# Sheet.net
KiCad netlist of a schematic drawn in Altium Designer
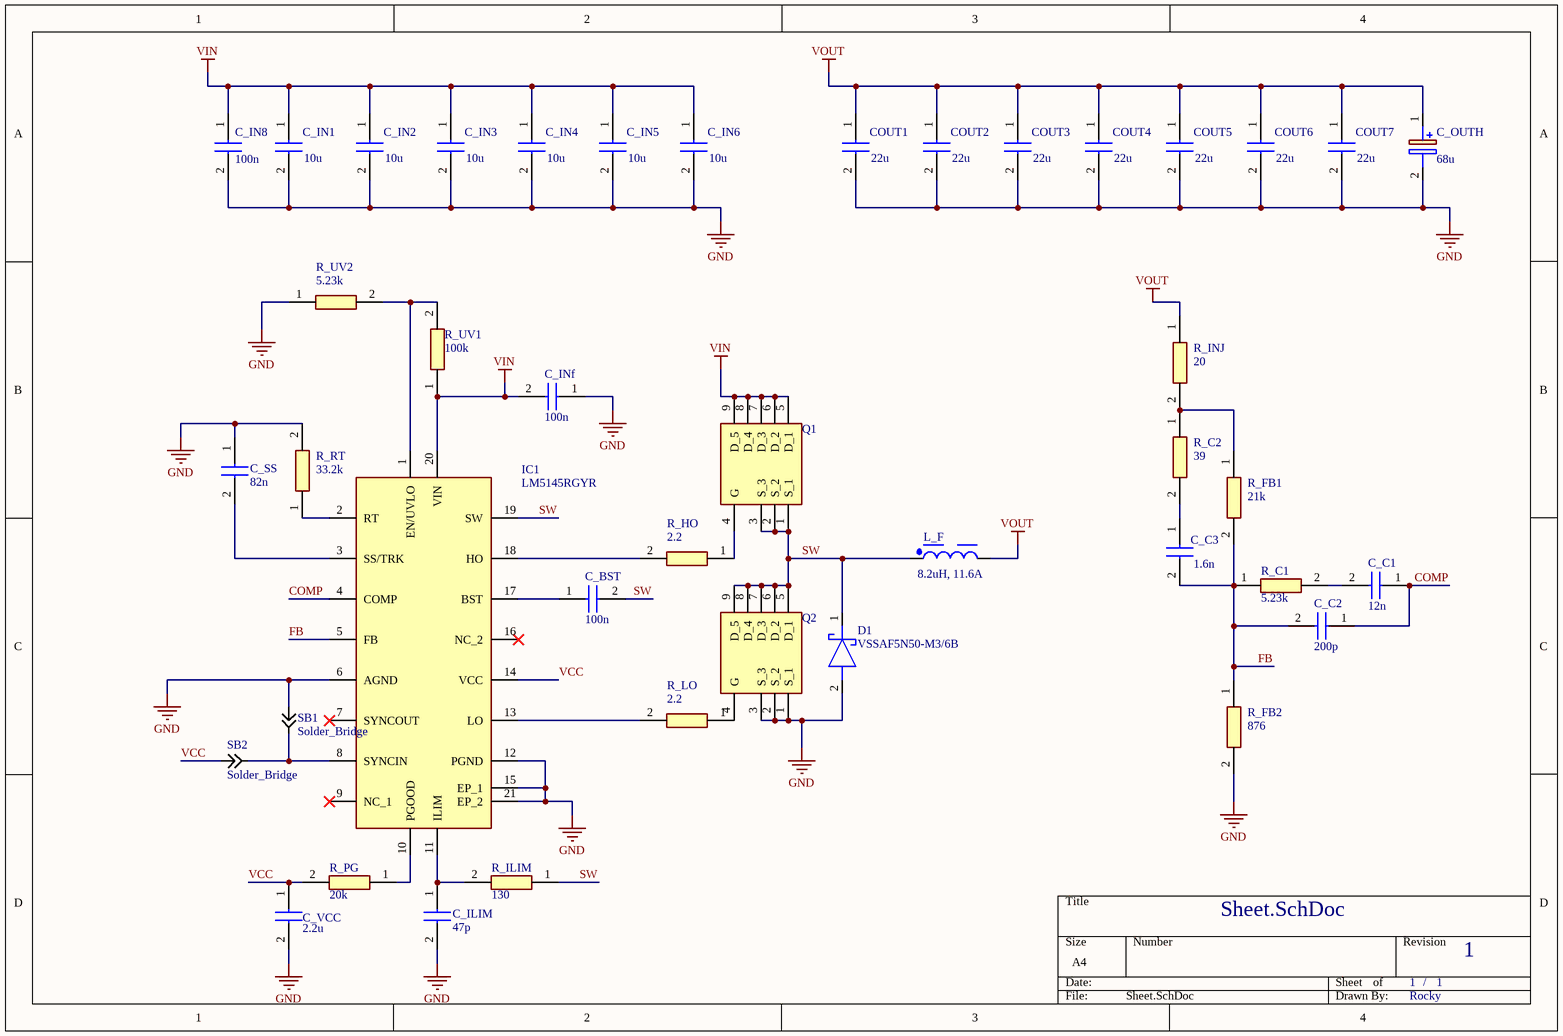
[diagram p0: Sheet.SchDoc]

(export (version "E")
  (design (tool "Eeschema 10.0.6"))
  (components
    (comp (ref "COUT1")
      (value "22u")
      (footprint "PcbLib:CAPC6153X390N")
      (description "Capacitor\r\nKCM55QR71H226KH13K")
      (fields
        (field (name "MANUFACTURER_PART_NUMBER") "KCM55QR71H226KH13K")
        (field (name "MOUSER PART NUMBER") "81-KCM5QR71H226KH13K")
      )
      (libsource (lib "*") (part "KCM55QR71H226KH13K"))
    )
    (comp (ref "COUT2")
      (value "22u")
      (footprint "PcbLib:CAPC6153X390N")
      (description "Capacitor\r\nKCM55QR71H226KH13K")
      (fields
        (field (name "MANUFACTURER_PART_NUMBER") "KCM55QR71H226KH13K")
        (field (name "MOUSER PART NUMBER") "81-KCM5QR71H226KH13K")
      )
      (libsource (lib "*") (part "KCM55QR71H226KH13K"))
    )
    (comp (ref "COUT3")
      (value "22u")
      (footprint "PcbLib:CAPC6153X390N")
      (description "Capacitor\r\nKCM55QR71H226KH13K")
      (fields
        (field (name "MANUFACTURER_PART_NUMBER") "KCM55QR71H226KH13K")
        (field (name "MOUSER PART NUMBER") "81-KCM5QR71H226KH13K")
      )
      (libsource (lib "*") (part "KCM55QR71H226KH13K"))
    )
    (comp (ref "COUT4")
      (value "22u")
      (footprint "PcbLib:CAPC6153X390N")
      (description "Capacitor\r\nKCM55QR71H226KH13K")
      (fields
        (field (name "MANUFACTURER_PART_NUMBER") "KCM55QR71H226KH13K")
        (field (name "MOUSER PART NUMBER") "81-KCM5QR71H226KH13K")
      )
      (libsource (lib "*") (part "KCM55QR71H226KH13K"))
    )
    (comp (ref "COUT5")
      (value "22u")
      (footprint "PcbLib:CAPC6153X390N")
      (description "Capacitor\r\nKCM55QR71H226KH13K")
      (fields
        (field (name "MANUFACTURER_PART_NUMBER") "KCM55QR71H226KH13K")
        (field (name "MOUSER PART NUMBER") "81-KCM5QR71H226KH13K")
      )
      (libsource (lib "*") (part "KCM55QR71H226KH13K"))
    )
    (comp (ref "COUT6")
      (value "22u")
      (footprint "PcbLib:CAPC6153X390N")
      (description "Capacitor\r\nKCM55QR71H226KH13K")
      (fields
        (field (name "MANUFACTURER_PART_NUMBER") "KCM55QR71H226KH13K")
        (field (name "MOUSER PART NUMBER") "81-KCM5QR71H226KH13K")
      )
      (libsource (lib "*") (part "KCM55QR71H226KH13K"))
    )
    (comp (ref "COUT7")
      (value "22u")
      (footprint "PcbLib:CAPC6153X390N")
      (description "Capacitor\r\nKCM55QR71H226KH13K")
      (fields
        (field (name "MANUFACTURER_PART_NUMBER") "KCM55QR71H226KH13K")
        (field (name "MOUSER PART NUMBER") "81-KCM5QR71H226KH13K")
      )
      (libsource (lib "*") (part "KCM55QR71H226KH13K"))
    )
    (comp (ref "C_BST")
      (value "100n")
      (footprint "PcbLib:CAPC1608X90N")
      (description "Capacitor")
      (fields
        (field (name "MANUFACTURER_PART_NUMBER") "GRM1885C1H101JA01D")
        (field (name "MOUSER PART NUMBER") "81-GRM39C101J50")
      )
      (libsource (lib "Schlib") (part "GRM1885C1H101JA01D"))
    )
    (comp (ref "C_C1")
      (value "12n")
      (footprint "PcbLib:CAPC1608X90N")
      (description "Capacitor")
      (fields
        (field (name "MANUFACTURER_PART_NUMBER") "06031A470JAT2A")
        (field (name "MOUSER PART NUMBER") "581-06031A470J")
      )
      (libsource (lib "*") (part "06031A470JAT2A"))
    )
    (comp (ref "C_C2")
      (value "200p")
      (footprint "PcbLib:CAPC1608X90N")
      (description "Capacitor")
      (fields
        (field (name "MANUFACTURER_PART_NUMBER") "06031A470JAT2A")
        (field (name "MOUSER PART NUMBER") "581-06031A470J")
      )
      (libsource (lib "*") (part "06031A470JAT2A"))
    )
    (comp (ref "C_C3")
      (value "1.6n")
      (footprint "PcbLib:CAPC1608X90N")
      (description "Capacitor")
      (fields
        (field (name "MANUFACTURER_PART_NUMBER") "06031A470JAT2A")
        (field (name "MOUSER PART NUMBER") "581-06031A470J")
      )
      (libsource (lib "*") (part "06031A470JAT2A"))
    )
    (comp (ref "C_ILIM")
      (value "47p")
      (footprint "PcbLib:CAPC1608X90N")
      (description "Capacitor")
      (fields
        (field (name "MANUFACTURER_PART_NUMBER") "06031A470JAT2A")
        (field (name "MOUSER PART NUMBER") "581-06031A470J")
      )
      (libsource (lib "*") (part "06031A470JAT2A"))
    )
    (comp (ref "C_IN1")
      (value "10u")
      (footprint "PcbLib:CAPC6153X390N")
      (description "Capacitor\r\nKRM55QR71J106KH01K")
      (fields
        (field (name "MANUFACTURER_PART_NUMBER") "KRM55QR71J106KH01K")
        (field (name "MOUSER PART NUMBER") "81-KRM55QR71J106KH1K")
      )
      (libsource (lib "*") (part "KRM55QR71J106KH01K"))
    )
    (comp (ref "C_IN2")
      (value "10u")
      (footprint "PcbLib:CAPC6153X390N")
      (description "Capacitor\r\nKRM55QR71J106KH01K")
      (fields
        (field (name "MANUFACTURER_PART_NUMBER") "KRM55QR71J106KH01K")
        (field (name "MOUSER PART NUMBER") "81-KRM55QR71J106KH1K")
      )
      (libsource (lib "*") (part "KRM55QR71J106KH01K"))
    )
    (comp (ref "C_IN3")
      (value "10u")
      (footprint "PcbLib:CAPC6153X390N")
      (description "Capacitor\r\nKRM55QR71J106KH01K")
      (fields
        (field (name "MANUFACTURER_PART_NUMBER") "KRM55QR71J106KH01K")
        (field (name "MOUSER PART NUMBER") "81-KRM55QR71J106KH1K")
      )
      (libsource (lib "*") (part "KRM55QR71J106KH01K"))
    )
    (comp (ref "C_IN4")
      (value "10u")
      (footprint "PcbLib:CAPC6153X390N")
      (description "Capacitor\r\nKRM55QR71J106KH01K")
      (fields
        (field (name "MANUFACTURER_PART_NUMBER") "KRM55QR71J106KH01K")
        (field (name "MOUSER PART NUMBER") "81-KRM55QR71J106KH1K")
      )
      (libsource (lib "*") (part "KRM55QR71J106KH01K"))
    )
    (comp (ref "C_IN5")
      (value "10u")
      (footprint "PcbLib:CAPC6153X390N")
      (description "Capacitor\r\nKRM55QR71J106KH01K")
      (fields
        (field (name "MANUFACTURER_PART_NUMBER") "KRM55QR71J106KH01K")
        (field (name "MOUSER PART NUMBER") "81-KRM55QR71J106KH1K")
      )
      (libsource (lib "*") (part "KRM55QR71J106KH01K"))
    )
    (comp (ref "C_IN6")
      (value "10u")
      (footprint "PcbLib:CAPC6153X390N")
      (description "Capacitor\r\nKRM55QR71J106KH01K")
      (fields
        (field (name "MANUFACTURER_PART_NUMBER") "KRM55QR71J106KH01K")
        (field (name "MOUSER PART NUMBER") "81-KRM55QR71J106KH1K")
      )
      (libsource (lib "*") (part "KRM55QR71J106KH01K"))
    )
    (comp (ref "C_IN8")
      (value "100n")
      (footprint "PcbLib:CAPC1608X90N")
      (description "Capacitor")
      (fields
        (field (name "MANUFACTURER_PART_NUMBER") "GRM1885C1H101JA01D")
        (field (name "MOUSER PART NUMBER") "81-GRM39C101J50")
      )
      (libsource (lib "Schlib") (part "GRM1885C1H101JA01D"))
    )
    (comp (ref "C_INf")
      (value "100n")
      (footprint "PcbLib:CAPC1608X90N")
      (description "Capacitor")
      (fields
        (field (name "MANUFACTURER_PART_NUMBER") "GRM1885C1H101JA01D")
        (field (name "MOUSER PART NUMBER") "81-GRM39C101J50")
      )
      (libsource (lib "Schlib") (part "GRM1885C1H101JA01D"))
    )
    (comp (ref "C_OUTH")
      (value "68u")
      (footprint "PcbLib:35TQS68ME2")
      (description "Capacitor Polarised")
      (fields (field (name "MANUFACTURER_PART_NUMBER") "35TQS68ME2"))
      (libsource (lib "*") (part "35TQS68ME2"))
    )
    (comp (ref "C_SS")
      (value "82n")
      (footprint "PcbLib:CAPC1608X90N")
      (description "Capacitor")
      (fields
        (field (name "MANUFACTURER_PART_NUMBER") "GRM1885C1H101JA01D")
        (field (name "MOUSER PART NUMBER") "81-GRM39C101J50")
      )
      (libsource (lib "Schlib") (part "GRM1885C1H101JA01D"))
    )
    (comp (ref "C_VCC")
      (value "2.2u")
      (footprint "PcbLib:CAPC1608X90N")
      (description "Capacitor")
      (fields
        (field (name "MANUFACTURER_PART_NUMBER") "06031A470JAT2A")
        (field (name "MOUSER PART NUMBER") "581-06031A470J")
      )
      (libsource (lib "*") (part "06031A470JAT2A"))
    )
    (comp (ref "D1")
      (value "VSSAF5N50-M3/6B")
      (footprint "PcbLib:SODFL5226X100N")
      (description "Schottky Diode")
      (fields
        (field (name "MANUFACTURER_PART_NUMBER") "VSSAF3M10-M3/H")
        (field (name "MOUSER PART NUMBER") "78-VSSAF3M10-M3/H")
      )
      (libsource (lib "Schlib") (part "VSSAF3M10-M3_H"))
    )
    (comp (ref "IC1")
      (value "LM5145RGYR")
      (footprint "PcbLib:RGY0020B")
      (description "Integrated Circuit")
      (fields (field (name "MOUSER PART NUMBER") "595-LM5145RGYR"))
      (libsource (lib "Schlib") (part "LM5145RGYR"))
    )
    (comp (ref "L_F")
      (value "8.2uH, 11.6A")
      (footprint "WE-LHCA_1365")
      (description "WE-LHCA Low Profile High Current Inductor, SMT, size 1365, 8.2uH, 11.6A")
      (fields
        (field (name "MANUFACTURER PART NUMBER") "784373865082")
        (field (name "MANUFACTURER") "Wurth Elektronik")
      )
      (libsource (lib "WE - Passive Components") (part "Inductor - 2"))
    )
    (comp (ref "Q1")
      (value "AON6512")
      (footprint "PcbLib:AON6414A")
      (description "MOSFET (P-Channel)")
      (libsource (lib "Schlib") (part "AON6512"))
    )
    (comp (ref "Q2")
      (value "AON6512")
      (footprint "PcbLib:AON6414A")
      (description "MOSFET (P-Channel)")
      (libsource (lib "Schlib") (part "AON6512"))
    )
    (comp (ref "R_C1")
      (value "5.23k")
      (footprint "PcbLib:RESC1608X55N")
      (description "Resistor")
      (fields
        (field (name "MANUFACTURER_PART_NUMBER") "ERJ-3EKF1270V")
        (field (name "MOUSER PART NUMBER") "667-ERJ-3EKF1270V")
      )
      (libsource (lib "") (part "ERJ-3EKF1270V_2"))
    )
    (comp (ref "R_C2")
      (value "39")
      (footprint "PcbLib:RESC1608X55N")
      (description "Resistor")
      (fields
        (field (name "MANUFACTURER_PART_NUMBER") "ERJ-3EKF1270V")
        (field (name "MOUSER PART NUMBER") "667-ERJ-3EKF1270V")
      )
      (libsource (lib "") (part "ERJ-3EKF1270V_1"))
    )
    (comp (ref "R_FB1")
      (value "21k")
      (footprint "PcbLib:RESC1608X55N")
      (description "Resistor")
      (fields
        (field (name "MANUFACTURER_PART_NUMBER") "ERJ-3EKF1270V")
        (field (name "MOUSER PART NUMBER") "667-ERJ-3EKF1270V")
      )
      (libsource (lib "") (part "ERJ-3EKF1270V_1"))
    )
    (comp (ref "R_FB2")
      (value "876")
      (footprint "PcbLib:RESC1608X55N")
      (description "Resistor")
      (fields
        (field (name "MANUFACTURER_PART_NUMBER") "ERJ-3EKF1270V")
        (field (name "MOUSER PART NUMBER") "667-ERJ-3EKF1270V")
      )
      (libsource (lib "") (part "ERJ-3EKF1270V_1"))
    )
    (comp (ref "R_HO")
      (value "2.2")
      (footprint "PcbLib:RESC1608X55N")
      (description "Resistor")
      (fields
        (field (name "MANUFACTURER_PART_NUMBER") "RC0603FR-105K1L")
        (field (name "MOUSER PART NUMBER") "603-RC0603FR-105K1L")
      )
      (libsource (lib "") (part "RC0603FR-105K1L_1"))
    )
    (comp (ref "R_ILIM")
      (value "130")
      (footprint "PcbLib:RESC1608X55N")
      (description "Resistor")
      (fields
        (field (name "MANUFACTURER_PART_NUMBER") "ERJ-3EKF1270V")
        (field (name "MOUSER PART NUMBER") "667-ERJ-3EKF1270V")
      )
      (libsource (lib "*") (part "ERJ-3EKF1270V"))
    )
    (comp (ref "R_INJ")
      (value "20")
      (footprint "PcbLib:RESC1608X55N")
      (description "Resistor")
      (fields
        (field (name "MANUFACTURER_PART_NUMBER") "ERJ-3EKF1270V")
        (field (name "MOUSER PART NUMBER") "667-ERJ-3EKF1270V")
      )
      (libsource (lib "") (part "ERJ-3EKF1270V_1"))
    )
    (comp (ref "R_LO")
      (value "2.2")
      (footprint "PcbLib:RESC1608X55N")
      (description "Resistor")
      (fields
        (field (name "MANUFACTURER_PART_NUMBER") "RC0603FR-105K1L")
        (field (name "MOUSER PART NUMBER") "603-RC0603FR-105K1L")
      )
      (libsource (lib "") (part "RC0603FR-105K1L_1"))
    )
    (comp (ref "R_PG")
      (value "20k")
      (footprint "PcbLib:RESC1608X55N")
      (description "Resistor")
      (fields
        (field (name "MANUFACTURER_PART_NUMBER") "ERJ-3EKF1270V")
        (field (name "MOUSER PART NUMBER") "667-ERJ-3EKF1270V")
      )
      (libsource (lib "*") (part "ERJ-3EKF1270V"))
    )
    (comp (ref "R_RT")
      (value "33.2k")
      (footprint "PcbLib:RESC1608X55N")
      (description "Resistor")
      (fields
        (field (name "MANUFACTURER_PART_NUMBER") "RC0603FR-105K1L")
        (field (name "MOUSER PART NUMBER") "603-RC0603FR-105K1L")
      )
      (libsource (lib "*") (part "RC0603FR-105K1L"))
    )
    (comp (ref "R_UV1")
      (value "100k")
      (footprint "PcbLib:RESC1608X55N")
      (description "Resistor")
      (fields
        (field (name "MANUFACTURER_PART_NUMBER") "RC0603FR-105K1L")
        (field (name "MOUSER PART NUMBER") "603-RC0603FR-105K1L")
      )
      (libsource (lib "Schlib") (part "RC0603FR-105K1L"))
    )
    (comp (ref "R_UV2")
      (value "5.23k")
      (footprint "PcbLib:RESC1608X55N")
      (description "Resistor")
      (fields
        (field (name "MANUFACTURER_PART_NUMBER") "RC0603FR-105K1L")
        (field (name "MOUSER PART NUMBER") "603-RC0603FR-105K1L")
      )
      (libsource (lib "") (part "RC0603FR-105K1L_1"))
    )
    (comp (ref "SB1")
      (value "Solder_Bridge")
      (footprint "Solderbridge")
      (libsource (lib "Schlib") (part "Solder_Bridge"))
    )
    (comp (ref "SB2")
      (value "Solder_Bridge")
      (footprint "Solderbridge")
      (libsource (lib "Schlib") (part "Solder_Bridge"))
    )
  )
  (nets
    (net (code "1") (name "/COMP") (class "Default")
      (node (ref "C_C1") (pin "1") (pinfunction "1_1") (pintype "passive"))
      (node (ref "C_C2") (pin "1") (pinfunction "1_1") (pintype "passive"))
      (node (ref "IC1") (pin "4") (pinfunction "COMP_4") (pintype "passive"))
    )
    (net (code "2") (name "/FB") (class "Default")
      (node (ref "C_C2") (pin "2") (pinfunction "2_2") (pintype "passive"))
      (node (ref "C_C3") (pin "2") (pinfunction "2_2") (pintype "passive"))
      (node (ref "IC1") (pin "5") (pinfunction "FB_5") (pintype "passive"))
      (node (ref "R_C1") (pin "1") (pinfunction "1_1") (pintype "passive"))
      (node (ref "R_FB1") (pin "2") (pinfunction "2_2") (pintype "passive"))
      (node (ref "R_FB2") (pin "1") (pinfunction "1_1") (pintype "passive"))
    )
    (net (code "3") (name "/SW") (class "Default")
      (node (ref "C_BST") (pin "2") (pinfunction "2_2") (pintype "passive"))
      (node (ref "D1") (pin "1") (pinfunction "K_1") (pintype "passive"))
      (node (ref "IC1") (pin "19") (pinfunction "SW_19") (pintype "passive"))
      (node (ref "L_F") (pin "1") (pinfunction "1_1") (pintype "passive"))
      (node (ref "Q1") (pin "1") (pinfunction "S_1_1") (pintype "passive"))
      (node (ref "Q1") (pin "2") (pinfunction "S_2_2") (pintype "passive"))
      (node (ref "Q1") (pin "3") (pinfunction "S_3_3") (pintype "passive"))
      (node (ref "Q2") (pin "5") (pinfunction "D_1_5") (pintype "passive"))
      (node (ref "Q2") (pin "6") (pinfunction "D_2_6") (pintype "passive"))
      (node (ref "Q2") (pin "7") (pinfunction "D_3_7") (pintype "passive"))
      (node (ref "Q2") (pin "8") (pinfunction "D_4_8") (pintype "passive"))
      (node (ref "Q2") (pin "9") (pinfunction "D_5_9") (pintype "passive"))
      (node (ref "R_ILIM") (pin "1") (pinfunction "1_1") (pintype "passive"))
    )
    (net (code "4") (name "/VCC") (class "Default")
      (node (ref "C_VCC") (pin "1") (pinfunction "1_1") (pintype "passive"))
      (node (ref "IC1") (pin "14") (pinfunction "VCC_14") (pintype "passive"))
      (node (ref "R_PG") (pin "2") (pinfunction "2_2") (pintype "passive"))
      (node (ref "SB2") (pin "1") (pinfunction "1_1") (pintype "passive"))
    )
    (net (code "5") (name "GND") (class "Default")
      (node (ref "COUT1") (pin "2") (pinfunction "2_2") (pintype "passive"))
      (node (ref "COUT2") (pin "2") (pinfunction "2_2") (pintype "passive"))
      (node (ref "COUT3") (pin "2") (pinfunction "2_2") (pintype "passive"))
      (node (ref "COUT4") (pin "2") (pinfunction "2_2") (pintype "passive"))
      (node (ref "COUT5") (pin "2") (pinfunction "2_2") (pintype "passive"))
      (node (ref "COUT6") (pin "2") (pinfunction "2_2") (pintype "passive"))
      (node (ref "COUT7") (pin "2") (pinfunction "2_2") (pintype "passive"))
      (node (ref "C_ILIM") (pin "2") (pinfunction "2_2") (pintype "passive"))
      (node (ref "C_IN1") (pin "2") (pinfunction "2_2") (pintype "passive"))
      (node (ref "C_IN2") (pin "2") (pinfunction "2_2") (pintype "passive"))
      (node (ref "C_IN3") (pin "2") (pinfunction "2_2") (pintype "passive"))
      (node (ref "C_IN4") (pin "2") (pinfunction "2_2") (pintype "passive"))
      (node (ref "C_IN5") (pin "2") (pinfunction "2_2") (pintype "passive"))
      (node (ref "C_IN6") (pin "2") (pinfunction "2_2") (pintype "passive"))
      (node (ref "C_IN8") (pin "2") (pinfunction "2_2") (pintype "passive"))
      (node (ref "C_INf") (pin "1") (pinfunction "1_1") (pintype "passive"))
      (node (ref "C_OUTH") (pin "2") (pinfunction "-_2") (pintype "passive"))
      (node (ref "C_SS") (pin "1") (pinfunction "1_1") (pintype "passive"))
      (node (ref "C_VCC") (pin "2") (pinfunction "2_2") (pintype "passive"))
      (node (ref "D1") (pin "2") (pinfunction "A_2") (pintype "passive"))
      (node (ref "IC1") (pin "12") (pinfunction "PGND_12") (pintype "passive"))
      (node (ref "IC1") (pin "15") (pinfunction "EP_1_15") (pintype "passive"))
      (node (ref "IC1") (pin "21") (pinfunction "EP_2_21") (pintype "passive"))
      (node (ref "IC1") (pin "6") (pinfunction "AGND_6") (pintype "passive"))
      (node (ref "Q2") (pin "1") (pinfunction "S_1_1") (pintype "passive"))
      (node (ref "Q2") (pin "2") (pinfunction "S_2_2") (pintype "passive"))
      (node (ref "Q2") (pin "3") (pinfunction "S_3_3") (pintype "passive"))
      (node (ref "R_FB2") (pin "2") (pinfunction "2_2") (pintype "passive"))
      (node (ref "R_RT") (pin "2") (pinfunction "2_2") (pintype "passive"))
      (node (ref "R_UV2") (pin "1") (pinfunction "1_1") (pintype "passive"))
      (node (ref "SB1") (pin "1") (pinfunction "1_1") (pintype "passive"))
    )
    (net (code "6") (name "Net-(C_C1-Pad2)") (class "Default")
      (node (ref "C_C1") (pin "2") (pinfunction "2_2") (pintype "passive"))
      (node (ref "R_C1") (pin "2") (pinfunction "2_2") (pintype "passive"))
    )
    (net (code "7") (name "Net-(C_C3-Pad1)") (class "Default")
      (node (ref "C_C3") (pin "1") (pinfunction "1_1") (pintype "passive"))
      (node (ref "R_C2") (pin "2") (pinfunction "2_2") (pintype "passive"))
    )
    (net (code "8") (name "Net-(IC1-BST)") (class "Default")
      (node (ref "C_BST") (pin "1") (pinfunction "1_1") (pintype "passive"))
      (node (ref "IC1") (pin "17") (pinfunction "BST_17") (pintype "passive"))
    )
    (net (code "9") (name "Net-(IC1-EN{slash}UVLO)") (class "Default")
      (node (ref "IC1") (pin "1") (pinfunction "EN/UVLO_1") (pintype "passive"))
      (node (ref "R_UV1") (pin "2") (pinfunction "2_2") (pintype "passive"))
      (node (ref "R_UV2") (pin "2") (pinfunction "2_2") (pintype "passive"))
    )
    (net (code "10") (name "Net-(IC1-HO)") (class "Default")
      (node (ref "IC1") (pin "18") (pinfunction "HO_18") (pintype "passive"))
      (node (ref "R_HO") (pin "2") (pinfunction "2_2") (pintype "passive"))
    )
    (net (code "11") (name "Net-(IC1-ILIM)") (class "Default")
      (node (ref "C_ILIM") (pin "1") (pinfunction "1_1") (pintype "passive"))
      (node (ref "IC1") (pin "11") (pinfunction "ILIM_11") (pintype "passive"))
      (node (ref "R_ILIM") (pin "2") (pinfunction "2_2") (pintype "passive"))
    )
    (net (code "12") (name "Net-(IC1-LO)") (class "Default")
      (node (ref "IC1") (pin "13") (pinfunction "LO_13") (pintype "passive"))
      (node (ref "R_LO") (pin "2") (pinfunction "2_2") (pintype "passive"))
    )
    (net (code "13") (name "Net-(IC1-PGOOD)") (class "Default")
      (node (ref "IC1") (pin "10") (pinfunction "PGOOD_10") (pintype "passive"))
      (node (ref "R_PG") (pin "1") (pinfunction "1_1") (pintype "passive"))
    )
    (net (code "14") (name "Net-(IC1-RT)") (class "Default")
      (node (ref "IC1") (pin "2") (pinfunction "RT_2") (pintype "passive"))
      (node (ref "R_RT") (pin "1") (pinfunction "1_1") (pintype "passive"))
    )
    (net (code "15") (name "Net-(IC1-SS{slash}TRK)") (class "Default")
      (node (ref "C_SS") (pin "2") (pinfunction "2_2") (pintype "passive"))
      (node (ref "IC1") (pin "3") (pinfunction "SS/TRK_3") (pintype "passive"))
    )
    (net (code "16") (name "Net-(IC1-SYNCIN)") (class "Default")
      (node (ref "IC1") (pin "8") (pinfunction "SYNCIN_8") (pintype "passive"))
      (node (ref "SB1") (pin "2") (pinfunction "2_2") (pintype "passive"))
      (node (ref "SB2") (pin "2") (pinfunction "2_2") (pintype "passive"))
    )
    (net (code "17") (name "Net-(Q1-G)") (class "Default")
      (node (ref "Q1") (pin "4") (pinfunction "G_4") (pintype "passive"))
      (node (ref "R_HO") (pin "1") (pinfunction "1_1") (pintype "passive"))
    )
    (net (code "18") (name "Net-(Q2-G)") (class "Default")
      (node (ref "Q2") (pin "4") (pinfunction "G_4") (pintype "passive"))
      (node (ref "R_LO") (pin "1") (pinfunction "1_1") (pintype "passive"))
    )
    (net (code "19") (name "Net-(R_C2-Pad1)") (class "Default")
      (node (ref "R_C2") (pin "1") (pinfunction "1_1") (pintype "passive"))
      (node (ref "R_FB1") (pin "1") (pinfunction "1_1") (pintype "passive"))
      (node (ref "R_INJ") (pin "2") (pinfunction "2_2") (pintype "passive"))
    )
    (net (code "20") (name "VIN") (class "Default")
      (node (ref "C_IN1") (pin "1") (pinfunction "1_1") (pintype "passive"))
      (node (ref "C_IN2") (pin "1") (pinfunction "1_1") (pintype "passive"))
      (node (ref "C_IN3") (pin "1") (pinfunction "1_1") (pintype "passive"))
      (node (ref "C_IN4") (pin "1") (pinfunction "1_1") (pintype "passive"))
      (node (ref "C_IN5") (pin "1") (pinfunction "1_1") (pintype "passive"))
      (node (ref "C_IN6") (pin "1") (pinfunction "1_1") (pintype "passive"))
      (node (ref "C_IN8") (pin "1") (pinfunction "1_1") (pintype "passive"))
      (node (ref "C_INf") (pin "2") (pinfunction "2_2") (pintype "passive"))
      (node (ref "IC1") (pin "20") (pinfunction "VIN_20") (pintype "passive"))
      (node (ref "Q1") (pin "5") (pinfunction "D_1_5") (pintype "passive"))
      (node (ref "Q1") (pin "6") (pinfunction "D_2_6") (pintype "passive"))
      (node (ref "Q1") (pin "7") (pinfunction "D_3_7") (pintype "passive"))
      (node (ref "Q1") (pin "8") (pinfunction "D_4_8") (pintype "passive"))
      (node (ref "Q1") (pin "9") (pinfunction "D_5_9") (pintype "passive"))
      (node (ref "R_UV1") (pin "1") (pinfunction "1_1") (pintype "passive"))
    )
    (net (code "21") (name "VOUT") (class "Default")
      (node (ref "COUT1") (pin "1") (pinfunction "1_1") (pintype "passive"))
      (node (ref "COUT2") (pin "1") (pinfunction "1_1") (pintype "passive"))
      (node (ref "COUT3") (pin "1") (pinfunction "1_1") (pintype "passive"))
      (node (ref "COUT4") (pin "1") (pinfunction "1_1") (pintype "passive"))
      (node (ref "COUT5") (pin "1") (pinfunction "1_1") (pintype "passive"))
      (node (ref "COUT6") (pin "1") (pinfunction "1_1") (pintype "passive"))
      (node (ref "COUT7") (pin "1") (pinfunction "1_1") (pintype "passive"))
      (node (ref "C_OUTH") (pin "1") (pinfunction "+_1") (pintype "passive"))
      (node (ref "L_F") (pin "2") (pinfunction "2_2") (pintype "passive"))
      (node (ref "R_INJ") (pin "1") (pinfunction "1_1") (pintype "passive"))
    )
    (net (code "22") (name "unconnected-(IC1-NC_1-Pad9)") (class "Default")
      (node (ref "IC1") (pin "9") (pinfunction "NC_1_9") (pintype "passive+no_connect"))
    )
    (net (code "23") (name "unconnected-(IC1-NC_2-Pad16)") (class "Default")
      (node (ref "IC1") (pin "16") (pinfunction "NC_2_16") (pintype "passive+no_connect"))
    )
    (net (code "24") (name "unconnected-(IC1-SYNCOUT-Pad7)") (class "Default")
      (node (ref "IC1") (pin "7") (pinfunction "SYNCOUT_7") (pintype "passive+no_connect"))
    )
  )
)
